# MCU.net
KiCad netlist of a schematic drawn in Altium Designer
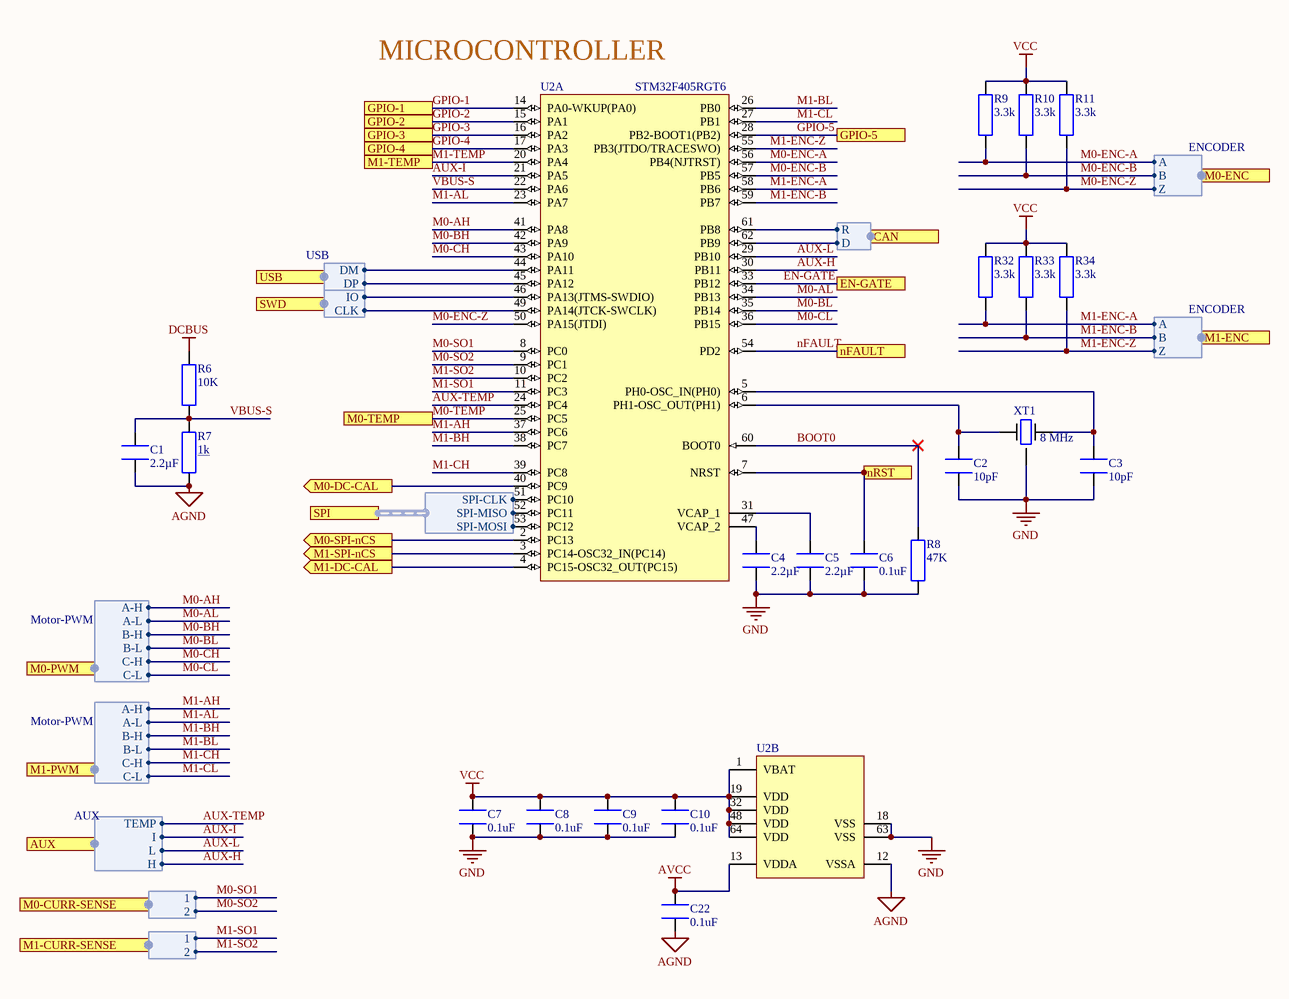
[diagram p0: MCU.SchDoc]

(export (version "E")
  (design (tool "Eeschema 10.0.6"))
  (components
    (comp (ref "C1")
      (value "2.2µF")
      (footprint "CAPC1608X09L")
      (description "CAP CER 2.2UF 16V X5R 0603")
      (fields
        (field (name "MANUFACTURER") "Murata Electronics North America")
        (field (name "MANUFACTURER PART NUMBER") "GRM188R61C225KE15D")
      )
      (libsource (lib "CustomComponents") (part "GRM188R61C225KE15D"))
    )
    (comp (ref "C2")
      (value "10pF")
      (footprint "CAPC1608X09L")
      (description "CAP CER 10PF 50V NP0 0603")
      (fields
        (field (name "MANUFACTURER") "Murata Electronics North America")
        (field (name "MANUFACTURER PART NUMBER") "GRM1885C1H100JA01D")
      )
      (libsource (lib "CustomComponents") (part "GRM1885C1H100JA01D"))
    )
    (comp (ref "C3")
      (value "10pF")
      (footprint "CAPC1608X09L")
      (description "CAP CER 10PF 50V NP0 0603")
      (fields
        (field (name "MANUFACTURER") "Murata Electronics North America")
        (field (name "MANUFACTURER PART NUMBER") "GRM1885C1H100JA01D")
      )
      (libsource (lib "CustomComponents") (part "GRM1885C1H100JA01D"))
    )
    (comp (ref "C4")
      (value "2.2µF")
      (footprint "CAPC1608X09L")
      (description "CAP CER 2.2UF 16V X5R 0603")
      (fields
        (field (name "MANUFACTURER") "Murata Electronics North America")
        (field (name "MANUFACTURER PART NUMBER") "GRM188R61C225KE15D")
      )
      (libsource (lib "CustomComponents") (part "GRM188R61C225KE15D"))
    )
    (comp (ref "C5")
      (value "2.2µF")
      (footprint "CAPC1608X09L")
      (description "CAP CER 2.2UF 16V X5R 0603")
      (fields
        (field (name "MANUFACTURER") "Murata Electronics North America")
        (field (name "MANUFACTURER PART NUMBER") "GRM188R61C225KE15D")
      )
      (libsource (lib "CustomComponents") (part "GRM188R61C225KE15D"))
    )
    (comp (ref "C6")
      (value "0.1uF")
      (footprint "CAPC1608X09L")
      (description "CAP CER 0.1UF 50V X7R 0603")
      (fields
        (field (name "MANUFACTURER") "Murata Electronics North America")
        (field (name "MANUFACTURER PART NUMBER") "GRM188R71H104KA93D")
      )
      (libsource (lib "CustomComponents") (part "GRM188R71H104KA93D"))
    )
    (comp (ref "C7")
      (value "0.1uF")
      (footprint "CAPC1608X09L")
      (description "CAP CER 0.1UF 50V X7R 0603")
      (fields
        (field (name "MANUFACTURER") "Murata Electronics North America")
        (field (name "MANUFACTURER PART NUMBER") "GRM188R71H104KA93D")
      )
      (libsource (lib "CustomComponents") (part "GRM188R71H104KA93D"))
    )
    (comp (ref "C8")
      (value "0.1uF")
      (footprint "CAPC1608X09L")
      (description "CAP CER 0.1UF 50V X7R 0603")
      (fields
        (field (name "MANUFACTURER") "Murata Electronics North America")
        (field (name "MANUFACTURER PART NUMBER") "GRM188R71H104KA93D")
      )
      (libsource (lib "CustomComponents") (part "GRM188R71H104KA93D"))
    )
    (comp (ref "C9")
      (value "0.1uF")
      (footprint "CAPC1608X09L")
      (description "CAP CER 0.1UF 50V X7R 0603")
      (fields
        (field (name "MANUFACTURER") "Murata Electronics North America")
        (field (name "MANUFACTURER PART NUMBER") "GRM188R71H104KA93D")
      )
      (libsource (lib "CustomComponents") (part "GRM188R71H104KA93D"))
    )
    (comp (ref "C10")
      (value "0.1uF")
      (footprint "CAPC1608X09L")
      (description "CAP CER 0.1UF 50V X7R 0603")
      (fields
        (field (name "MANUFACTURER") "Murata Electronics North America")
        (field (name "MANUFACTURER PART NUMBER") "GRM188R71H104KA93D")
      )
      (libsource (lib "CustomComponents") (part "GRM188R71H104KA93D"))
    )
    (comp (ref "C22")
      (value "0.1uF")
      (footprint "CAPC1608X09L")
      (description "CAP CER 0.1UF 50V X7R 0603")
      (fields
        (field (name "MANUFACTURER") "Murata Electronics North America")
        (field (name "MANUFACTURER PART NUMBER") "GRM188R71H104KA93D")
      )
      (libsource (lib "CustomComponents") (part "GRM188R71H104KA93D"))
    )
    (comp (ref "R6")
      (value "10K")
      (footprint "RESC1608X55N")
      (description "RES SMD 10K OHM 1% 1/10W 0603")
      (fields
        (field (name "MANUFACTURER") "Yageo")
        (field (name "MANUFACTURER PART NUMBER") "RC0603FR-0710KL")
      )
      (libsource (lib "CustomComponents") (part "RC0603FR-0710KL"))
    )
    (comp (ref "R7")
      (value "1k")
      (footprint "RESC1608X55N")
      (description "RES SMD 1K OHM 1% 1/10W 0603")
      (fields (field (name "MANUFACTURER") "Yageo") (field (name "TOLERANCE") "±1%"))
      (libsource (lib "CustomComponents") (part "RC0603FR-071KL"))
    )
    (comp (ref "R8")
      (value "47K")
      (footprint "RESC1608X55N")
      (description "RES SMD 47K OHM 1% 1/10W 0603")
      (fields
        (field (name "MANUFACTURER") "Yageo")
        (field (name "MANUFACTURER PART NUMBER") "RC0603FR-0747KL")
      )
      (libsource (lib "CustomComponents") (part "RC0603FR-0747KL"))
    )
    (comp (ref "R9")
      (value "3.3k")
      (footprint "RESC1608X55N")
      (description "RES SMD 3.3K OHM 1% 1/10W 0603")
      (fields (field (name "MANUFACTURER") "Yageo") (field (name "TOLERANCE") "±1%"))
      (libsource (lib "CustomComponents") (part "RC0603FR-073K3L"))
    )
    (comp (ref "R10")
      (value "3.3k")
      (footprint "RESC1608X55N")
      (description "RES SMD 3.3K OHM 1% 1/10W 0603")
      (fields (field (name "MANUFACTURER") "Yageo") (field (name "TOLERANCE") "±1%"))
      (libsource (lib "CustomComponents") (part "RC0603FR-073K3L"))
    )
    (comp (ref "R11")
      (value "3.3k")
      (footprint "RESC1608X55N")
      (description "RES SMD 3.3K OHM 1% 1/10W 0603")
      (fields (field (name "MANUFACTURER") "Yageo") (field (name "TOLERANCE") "±1%"))
      (libsource (lib "CustomComponents") (part "RC0603FR-073K3L"))
    )
    (comp (ref "R32")
      (value "3.3k")
      (footprint "RESC1608X55N")
      (description "RES SMD 3.3K OHM 1% 1/10W 0603")
      (fields (field (name "MANUFACTURER") "Yageo") (field (name "TOLERANCE") "±1%"))
      (libsource (lib "CustomComponents") (part "RC0603FR-073K3L"))
    )
    (comp (ref "R33")
      (value "3.3k")
      (footprint "RESC1608X55N")
      (description "RES SMD 3.3K OHM 1% 1/10W 0603")
      (fields (field (name "MANUFACTURER") "Yageo") (field (name "TOLERANCE") "±1%"))
      (libsource (lib "CustomComponents") (part "RC0603FR-073K3L"))
    )
    (comp (ref "R34")
      (value "3.3k")
      (footprint "RESC1608X55N")
      (description "RES SMD 3.3K OHM 1% 1/10W 0603")
      (fields (field (name "MANUFACTURER") "Yageo") (field (name "TOLERANCE") "±1%"))
      (libsource (lib "CustomComponents") (part "RC0603FR-073K3L"))
    )
    (comp (ref "U2")
      (value "~")
      (footprint "STM-LQFP64_N")
      (fields (field (name "MANUFACTURER") "STMicroelectronics") (field (name "PARTNUMBER") "STM32F405RGT6"))
      (libsource (lib "STMicroelectronics STM32 F4") (part "STM32F405RGT6"))
    )
    (comp (ref "XT1")
      (value "8 MHz")
      (footprint "DFN220P320X110-4N")
      (description "Crystal 8MHz ±10ppm 10pF 200 Ohm -10°C ~ 60°C Surface Mount 4-SMD, No Lead (DFN, LCC)")
      (fields
        (field (name "MANUFACTURER") "Abracon LLC")
        (field (name "MANUFACTURER PART NUMBER") "ABM3B-8.000MHZ-10-1-U-T")
      )
      (libsource (lib "CustomComponents") (part "ABM3B-8.000MHZ-10-1-U-T"))
    )
  )
  (nets
    (net (code "9") (name "/AUX-H") (class "Default")
      (node (ref "U2") (pin "30") (pinfunction "PB11_30") (pintype "bidirectional"))
    )
    (net (code "10") (name "/AUX-I") (class "Default")
      (node (ref "U2") (pin "21") (pinfunction "PA5_21") (pintype "bidirectional"))
    )
    (net (code "11") (name "/AUX-L") (class "Default")
      (node (ref "U2") (pin "29") (pinfunction "PB10_29") (pintype "bidirectional"))
    )
    (net (code "12") (name "/AUX-TEMP") (class "Default")
      (node (ref "U2") (pin "24") (pinfunction "PC4_24") (pintype "bidirectional"))
    )
    (net (code "13") (name "/BOOT0") (class "Default")
      (node (ref "R8") (pin "2") (pinfunction "0_2") (pintype "passive"))
      (node (ref "U2") (pin "60") (pinfunction "BOOT0_60") (pintype "input"))
    )
    (net (code "14") (name "/CLK") (class "Default")
      (node (ref "U2") (pin "49") (pinfunction "PA14(JTCK-SWCLK)_49") (pintype "bidirectional"))
    )
    (net (code "15") (name "/D") (class "Default")
      (node (ref "U2") (pin "62") (pinfunction "PB9_62") (pintype "bidirectional"))
    )
    (net (code "16") (name "/DM") (class "Default")
      (node (ref "U2") (pin "44") (pinfunction "PA11_44") (pintype "bidirectional"))
    )
    (net (code "17") (name "/DP") (class "Default")
      (node (ref "U2") (pin "45") (pinfunction "PA12_45") (pintype "bidirectional"))
    )
    (net (code "18") (name "/EN-GATE") (class "Default")
      (node (ref "U2") (pin "33") (pinfunction "PB12_33") (pintype "bidirectional"))
    )
    (net (code "19") (name "/GPIO-1") (class "Default")
      (node (ref "U2") (pin "14") (pinfunction "PA0-WKUP(PA0)_14") (pintype "bidirectional"))
    )
    (net (code "20") (name "/GPIO-2") (class "Default")
      (node (ref "U2") (pin "15") (pinfunction "PA1_15") (pintype "bidirectional"))
    )
    (net (code "21") (name "/GPIO-3") (class "Default")
      (node (ref "U2") (pin "16") (pinfunction "PA2_16") (pintype "bidirectional"))
    )
    (net (code "22") (name "/GPIO-4") (class "Default")
      (node (ref "U2") (pin "17") (pinfunction "PA3_17") (pintype "bidirectional"))
    )
    (net (code "23") (name "/GPIO-5") (class "Default")
      (node (ref "U2") (pin "28") (pinfunction "PB2-BOOT1(PB2)_28") (pintype "bidirectional"))
    )
    (net (code "24") (name "/IO") (class "Default")
      (node (ref "U2") (pin "46") (pinfunction "PA13(JTMS-SWDIO)_46") (pintype "bidirectional"))
    )
    (net (code "25") (name "/M0-AH") (class "Default")
      (node (ref "U2") (pin "41") (pinfunction "PA8_41") (pintype "bidirectional"))
    )
    (net (code "26") (name "/M0-AL") (class "Default")
      (node (ref "U2") (pin "34") (pinfunction "PB13_34") (pintype "bidirectional"))
    )
    (net (code "27") (name "/M0-BH") (class "Default")
      (node (ref "U2") (pin "42") (pinfunction "PA9_42") (pintype "bidirectional"))
    )
    (net (code "28") (name "/M0-BL") (class "Default")
      (node (ref "U2") (pin "35") (pinfunction "PB14_35") (pintype "bidirectional"))
    )
    (net (code "29") (name "/M0-CH") (class "Default")
      (node (ref "U2") (pin "43") (pinfunction "PA10_43") (pintype "bidirectional"))
    )
    (net (code "30") (name "/M0-CL") (class "Default")
      (node (ref "U2") (pin "36") (pinfunction "PB15_36") (pintype "bidirectional"))
    )
    (net (code "31") (name "/M0-DC-CAL") (class "Default")
      (node (ref "U2") (pin "40") (pinfunction "PC9_40") (pintype "bidirectional"))
    )
    (net (code "32") (name "/M0-ENC-A") (class "Default")
      (node (ref "R9") (pin "1") (pinfunction "0_1") (pintype "passive"))
      (node (ref "U2") (pin "56") (pinfunction "PB4(NJTRST)_56") (pintype "bidirectional"))
    )
    (net (code "33") (name "/M0-ENC-B") (class "Default")
      (node (ref "R10") (pin "1") (pinfunction "0_1") (pintype "passive"))
      (node (ref "U2") (pin "57") (pinfunction "PB5_57") (pintype "bidirectional"))
    )
    (net (code "34") (name "/M0-ENC-Z") (class "Default")
      (node (ref "R11") (pin "1") (pinfunction "0_1") (pintype "passive"))
      (node (ref "U2") (pin "50") (pinfunction "PA15(JTDI)_50") (pintype "bidirectional"))
    )
    (net (code "35") (name "/M0-SO1") (class "Default")
      (node (ref "U2") (pin "8") (pinfunction "PC0_8") (pintype "bidirectional"))
    )
    (net (code "36") (name "/M0-SO2") (class "Default")
      (node (ref "U2") (pin "9") (pinfunction "PC1_9") (pintype "bidirectional"))
    )
    (net (code "37") (name "/M0-SPI-nCS") (class "Default")
      (node (ref "U2") (pin "2") (pinfunction "PC13_2") (pintype "bidirectional"))
    )
    (net (code "38") (name "/M0-TEMP") (class "Default")
      (node (ref "U2") (pin "25") (pinfunction "PC5_25") (pintype "bidirectional"))
    )
    (net (code "39") (name "/M1-AH") (class "Default")
      (node (ref "U2") (pin "37") (pinfunction "PC6_37") (pintype "bidirectional"))
    )
    (net (code "40") (name "/M1-AL") (class "Default")
      (node (ref "U2") (pin "23") (pinfunction "PA7_23") (pintype "bidirectional"))
    )
    (net (code "41") (name "/M1-BH") (class "Default")
      (node (ref "U2") (pin "38") (pinfunction "PC7_38") (pintype "bidirectional"))
    )
    (net (code "42") (name "/M1-BL") (class "Default")
      (node (ref "U2") (pin "26") (pinfunction "PB0_26") (pintype "bidirectional"))
    )
    (net (code "43") (name "/M1-CH") (class "Default")
      (node (ref "U2") (pin "39") (pinfunction "PC8_39") (pintype "bidirectional"))
    )
    (net (code "44") (name "/M1-CL") (class "Default")
      (node (ref "U2") (pin "27") (pinfunction "PB1_27") (pintype "bidirectional"))
    )
    (net (code "45") (name "/M1-DC-CAL") (class "Default")
      (node (ref "U2") (pin "4") (pinfunction "PC15-OSC32_OUT(PC15)_4") (pintype "bidirectional"))
    )
    (net (code "46") (name "/M1-ENC-A") (class "Default")
      (node (ref "R32") (pin "2") (pinfunction "0_2") (pintype "passive"))
      (node (ref "U2") (pin "58") (pinfunction "PB6_58") (pintype "bidirectional"))
    )
    (net (code "47") (name "/M1-ENC-B") (class "Default")
      (node (ref "R33") (pin "2") (pinfunction "0_2") (pintype "passive"))
      (node (ref "U2") (pin "59") (pinfunction "PB7_59") (pintype "bidirectional"))
    )
    (net (code "48") (name "/M1-ENC-Z") (class "Default")
      (node (ref "R34") (pin "2") (pinfunction "0_2") (pintype "passive"))
      (node (ref "U2") (pin "55") (pinfunction "PB3(JTDO/TRACESWO)_55") (pintype "bidirectional"))
    )
    (net (code "49") (name "/M1-SO1") (class "Default")
      (node (ref "U2") (pin "11") (pinfunction "PC3_11") (pintype "bidirectional"))
    )
    (net (code "50") (name "/M1-SO2") (class "Default")
      (node (ref "U2") (pin "10") (pinfunction "PC2_10") (pintype "bidirectional"))
    )
    (net (code "51") (name "/M1-SPI-nCS") (class "Default")
      (node (ref "U2") (pin "3") (pinfunction "PC14-OSC32_IN(PC14)_3") (pintype "bidirectional"))
    )
    (net (code "52") (name "/M1-TEMP") (class "Default")
      (node (ref "U2") (pin "20") (pinfunction "PA4_20") (pintype "bidirectional"))
    )
    (net (code "53") (name "/R") (class "Default")
      (node (ref "U2") (pin "61") (pinfunction "PB8_61") (pintype "bidirectional"))
    )
    (net (code "54") (name "/SPI-CLK") (class "Default")
      (node (ref "U2") (pin "51") (pinfunction "PC10_51") (pintype "bidirectional"))
    )
    (net (code "55") (name "/SPI-MISO") (class "Default")
      (node (ref "U2") (pin "52") (pinfunction "PC11_52") (pintype "bidirectional"))
    )
    (net (code "56") (name "/SPI-MOSI") (class "Default")
      (node (ref "U2") (pin "53") (pinfunction "PC12_53") (pintype "bidirectional"))
    )
    (net (code "57") (name "/VBUS-S") (class "Default")
      (node (ref "C1") (pin "2") (pinfunction "2_2") (pintype "passive"))
      (node (ref "R6") (pin "1") (pinfunction "0_1") (pintype "passive"))
      (node (ref "R7") (pin "2") (pinfunction "0_2") (pintype "passive"))
      (node (ref "U2") (pin "22") (pinfunction "PA6_22") (pintype "bidirectional"))
    )
    (net (code "58") (name "/nFAULT") (class "Default")
      (node (ref "U2") (pin "54") (pinfunction "PD2_54") (pintype "bidirectional"))
    )
    (net (code "59") (name "/nRST") (class "Default")
      (node (ref "C6") (pin "2") (pinfunction "2_2") (pintype "passive"))
      (node (ref "U2") (pin "7") (pinfunction "NRST_7") (pintype "bidirectional"))
    )
    (net (code "68") (name "AGND") (class "Default")
      (node (ref "C1") (pin "1") (pinfunction "1_1") (pintype "passive"))
      (node (ref "C22") (pin "2") (pinfunction "2_2") (pintype "passive"))
      (node (ref "R7") (pin "1") (pinfunction "0_1") (pintype "passive"))
      (node (ref "U2") (pin "12") (pinfunction "VSSA_12") (pintype "power_in"))
    )
    (net (code "69") (name "AVCC") (class "Default")
      (node (ref "C22") (pin "1") (pinfunction "1_1") (pintype "passive"))
      (node (ref "U2") (pin "13") (pinfunction "VDDA_13") (pintype "power_in"))
    )
    (net (code "70") (name "DCBUS") (class "Default")
      (node (ref "R6") (pin "2") (pinfunction "0_2") (pintype "passive"))
    )
    (net (code "71") (name "GND") (class "Default")
      (node (ref "C10") (pin "2") (pinfunction "2_2") (pintype "passive"))
      (node (ref "C2") (pin "2") (pinfunction "2_2") (pintype "passive"))
      (node (ref "C3") (pin "2") (pinfunction "2_2") (pintype "passive"))
      (node (ref "C4") (pin "1") (pinfunction "1_1") (pintype "passive"))
      (node (ref "C5") (pin "1") (pinfunction "1_1") (pintype "passive"))
      (node (ref "C6") (pin "1") (pinfunction "1_1") (pintype "passive"))
      (node (ref "C7") (pin "2") (pinfunction "2_2") (pintype "passive"))
      (node (ref "C8") (pin "2") (pinfunction "2_2") (pintype "passive"))
      (node (ref "C9") (pin "2") (pinfunction "2_2") (pintype "passive"))
      (node (ref "R8") (pin "1") (pinfunction "0_1") (pintype "passive"))
      (node (ref "U2") (pin "18") (pinfunction "VSS_18") (pintype "power_in"))
      (node (ref "U2") (pin "63") (pinfunction "VSS_63") (pintype "power_in"))
      (node (ref "XT1") (pin "G") (pintype "passive"))
    )
    (net (code "72") (name "Net-(U2A-PH0-OSC_IN(PH0))") (class "Default")
      (node (ref "C3") (pin "1") (pinfunction "1_1") (pintype "passive"))
      (node (ref "U2") (pin "5") (pinfunction "PH0-OSC_IN(PH0)_5") (pintype "bidirectional"))
      (node (ref "XT1") (pin "3") (pintype "passive"))
    )
    (net (code "73") (name "Net-(U2A-PH1-OSC_OUT(PH1))") (class "Default")
      (node (ref "C2") (pin "1") (pinfunction "1_1") (pintype "passive"))
      (node (ref "U2") (pin "6") (pinfunction "PH1-OSC_OUT(PH1)_6") (pintype "bidirectional"))
      (node (ref "XT1") (pin "1") (pintype "passive"))
    )
    (net (code "74") (name "Net-(U2A-VCAP_1)") (class "Default")
      (node (ref "C5") (pin "2") (pinfunction "2_2") (pintype "passive"))
      (node (ref "U2") (pin "31") (pinfunction "VCAP_1_31") (pintype "power_in"))
    )
    (net (code "75") (name "Net-(U2A-VCAP_2)") (class "Default")
      (node (ref "C4") (pin "2") (pinfunction "2_2") (pintype "passive"))
      (node (ref "U2") (pin "47") (pinfunction "VCAP_2_47") (pintype "power_in"))
    )
    (net (code "76") (name "VCC") (class "Default")
      (node (ref "C10") (pin "1") (pinfunction "1_1") (pintype "passive"))
      (node (ref "C7") (pin "1") (pinfunction "1_1") (pintype "passive"))
      (node (ref "C8") (pin "1") (pinfunction "1_1") (pintype "passive"))
      (node (ref "C9") (pin "1") (pinfunction "1_1") (pintype "passive"))
      (node (ref "R10") (pin "2") (pinfunction "0_2") (pintype "passive"))
      (node (ref "R11") (pin "2") (pinfunction "0_2") (pintype "passive"))
      (node (ref "R32") (pin "1") (pinfunction "0_1") (pintype "passive"))
      (node (ref "R33") (pin "1") (pinfunction "0_1") (pintype "passive"))
      (node (ref "R34") (pin "1") (pinfunction "0_1") (pintype "passive"))
      (node (ref "R9") (pin "2") (pinfunction "0_2") (pintype "passive"))
      (node (ref "U2") (pin "1") (pinfunction "VBAT_1") (pintype "power_in"))
      (node (ref "U2") (pin "19") (pinfunction "VDD_19") (pintype "power_in"))
      (node (ref "U2") (pin "32") (pinfunction "VDD_32") (pintype "power_in"))
      (node (ref "U2") (pin "48") (pinfunction "VDD_48") (pintype "power_in"))
      (node (ref "U2") (pin "64") (pinfunction "VDD_64") (pintype "power_in"))
    )
  )
)
